# experimental.net
KiCad netlist of a schematic drawn in EAGLE
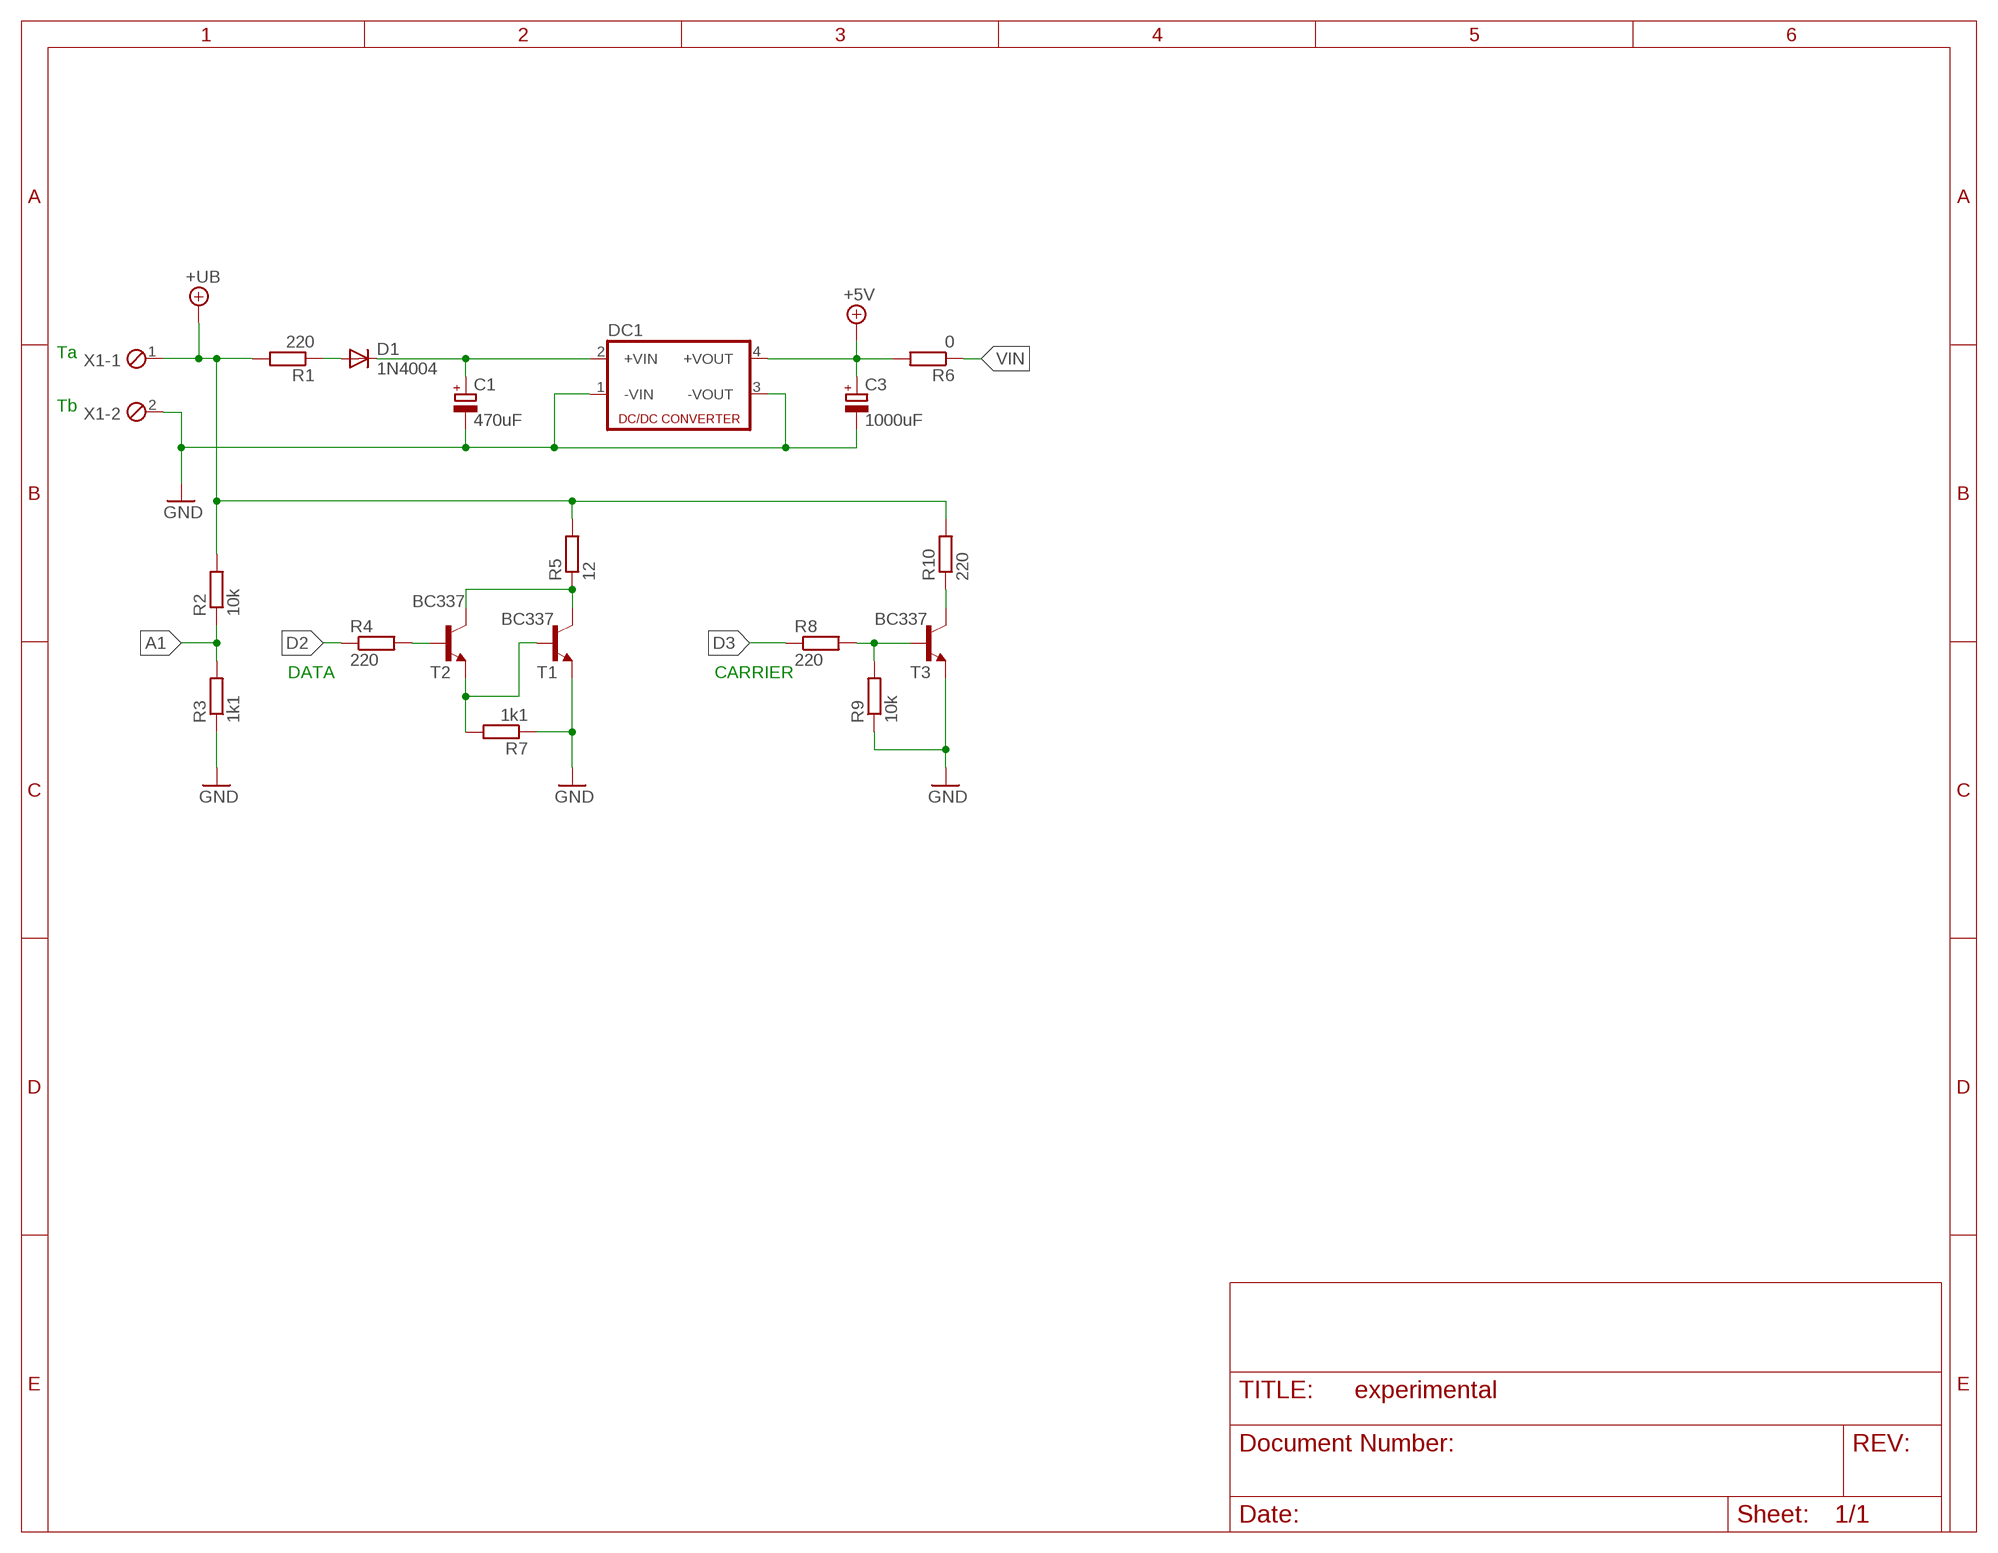
[diagram p0: schematic, sheet 1]

(export (version "E")
  (design (tool "Eeschema 10.0.6"))
  (components
    (comp (ref "C1")
      (value "470uF")
      (footprint "eagle-import:EB20D")
      (libsource (lib "eagle-import") (part "CPOL-EUE10-20"))
    )
    (comp (ref "C3")
      (value "1000uF")
      (footprint "eagle-import:EB20D")
      (libsource (lib "eagle-import") (part "CPOL-EUE10-20"))
    )
    (comp (ref "D1")
      (value "1N4004")
      (footprint "eagle-import:DO41-10")
      (libsource (lib "eagle-import") (part "1N4004"))
    )
    (comp (ref "DC1")
      (value "NME")
      (footprint "eagle-import:NME")
      (fields (field (name "MF") "C & D TECHNOLOGIES, INC") (field (name "MPN") "NME1205D"))
      (libsource (lib "eagle-import") (part "NME"))
    )
    (comp (ref "R1")
      (value "220")
      (footprint "eagle-import:0204_7")
      (libsource (lib "eagle-import") (part "R-EU_0204/7"))
    )
    (comp (ref "R2")
      (value "10k")
      (footprint "eagle-import:0204_7")
      (libsource (lib "eagle-import") (part "R-EU_0204/7"))
    )
    (comp (ref "R3")
      (value "1k1")
      (footprint "eagle-import:0204_7")
      (libsource (lib "eagle-import") (part "R-EU_0204/7"))
    )
    (comp (ref "R4")
      (value "220")
      (footprint "eagle-import:0204_7")
      (libsource (lib "eagle-import") (part "R-EU_0204/7"))
    )
    (comp (ref "R5")
      (value "12")
      (footprint "eagle-import:0204_7")
      (libsource (lib "eagle-import") (part "R-EU_0204/7"))
    )
    (comp (ref "R6")
      (value "0")
      (footprint "eagle-import:0204_7")
      (libsource (lib "eagle-import") (part "R-EU_0204/7"))
    )
    (comp (ref "R7")
      (value "1k1")
      (footprint "eagle-import:0204_7")
      (libsource (lib "eagle-import") (part "R-EU_0204/7"))
    )
    (comp (ref "R8")
      (value "220")
      (footprint "eagle-import:0204_7")
      (libsource (lib "eagle-import") (part "R-EU_0204/7"))
    )
    (comp (ref "R9")
      (value "10k")
      (footprint "eagle-import:0204_7")
      (libsource (lib "eagle-import") (part "R-EU_0204/7"))
    )
    (comp (ref "R10")
      (value "220")
      (footprint "eagle-import:0204_7")
      (libsource (lib "eagle-import") (part "R-EU_0204/7"))
    )
    (comp (ref "T1")
      (value "BC337")
      (footprint "eagle-import:TO92")
      (libsource (lib "eagle-import") (part "BC337"))
    )
    (comp (ref "T2")
      (value "BC337")
      (footprint "eagle-import:TO92")
      (libsource (lib "eagle-import") (part "BC337"))
    )
    (comp (ref "T3")
      (value "BC337")
      (footprint "eagle-import:TO92")
      (libsource (lib "eagle-import") (part "BC337"))
    )
    (comp (ref "X1")
      (value "MPT2")
      (footprint "eagle-import:2POL254")
      (libsource (lib "eagle-import") (part "MPT2"))
    )
  )
  (nets
    (net (code "1") (name "+5V") (class "Default")
      (node (ref "C3") (pin "+") (pinfunction "+_+") (pintype "passive"))
      (node (ref "DC1") (pin "4") (pinfunction "+VOUT_4") (pintype "passive"))
      (node (ref "R6") (pin "2") (pinfunction "2_2") (pintype "passive"))
    )
    (net (code "2") (name "+UB") (class "Default")
      (node (ref "R1") (pin "2") (pinfunction "2_2") (pintype "passive"))
      (node (ref "R10") (pin "2") (pinfunction "2_2") (pintype "passive"))
      (node (ref "R2") (pin "2") (pinfunction "2_2") (pintype "passive"))
      (node (ref "R5") (pin "2") (pinfunction "2_2") (pintype "passive"))
      (node (ref "X1") (pin "1") (pinfunction "1_1") (pintype "passive"))
    )
    (net (code "3") (name "A1") (class "Default")
      (node (ref "R2") (pin "1") (pinfunction "1_1") (pintype "passive"))
      (node (ref "R3") (pin "2") (pinfunction "2_2") (pintype "passive"))
    )
    (net (code "4") (name "D2") (class "Default")
      (node (ref "R4") (pin "1") (pinfunction "1_1") (pintype "passive"))
    )
    (net (code "5") (name "D3") (class "Default")
      (node (ref "R8") (pin "1") (pinfunction "1_1") (pintype "passive"))
    )
    (net (code "6") (name "GND") (class "Default")
      (node (ref "C1") (pin "-") (pinfunction "-_-") (pintype "passive"))
      (node (ref "C3") (pin "-") (pinfunction "-_-") (pintype "passive"))
      (node (ref "DC1") (pin "1") (pinfunction "-VIN_1") (pintype "passive"))
      (node (ref "DC1") (pin "3") (pinfunction "-VOUT_3") (pintype "passive"))
      (node (ref "R3") (pin "1") (pinfunction "1_1") (pintype "passive"))
      (node (ref "R7") (pin "1") (pinfunction "1_1") (pintype "passive"))
      (node (ref "R9") (pin "1") (pinfunction "1_1") (pintype "passive"))
      (node (ref "T1") (pin "1") (pinfunction "E_1") (pintype "passive"))
      (node (ref "T3") (pin "1") (pinfunction "E_1") (pintype "passive"))
      (node (ref "X1") (pin "2") (pinfunction "1_2") (pintype "passive"))
    )
    (net (code "7") (name "Net-(D1-PadA)") (class "Default")
      (node (ref "D1") (pin "A") (pinfunction "A_A") (pintype "passive"))
      (node (ref "R1") (pin "1") (pinfunction "1_1") (pintype "passive"))
    )
    (net (code "8") (name "Net-(DC1-+VIN)") (class "Default")
      (node (ref "C1") (pin "+") (pinfunction "+_+") (pintype "passive"))
      (node (ref "D1") (pin "C") (pinfunction "C_C") (pintype "passive"))
      (node (ref "DC1") (pin "2") (pinfunction "+VIN_2") (pintype "passive"))
    )
    (net (code "9") (name "Net-(T1-B)") (class "Default")
      (node (ref "R7") (pin "2") (pinfunction "2_2") (pintype "passive"))
      (node (ref "T1") (pin "2") (pinfunction "B_2") (pintype "passive"))
      (node (ref "T2") (pin "1") (pinfunction "E_1") (pintype "passive"))
    )
    (net (code "10") (name "Net-(T1-C)") (class "Default")
      (node (ref "R5") (pin "1") (pinfunction "1_1") (pintype "passive"))
      (node (ref "T1") (pin "3") (pinfunction "C_3") (pintype "passive"))
      (node (ref "T2") (pin "3") (pinfunction "C_3") (pintype "passive"))
    )
    (net (code "11") (name "Net-(T2-B)") (class "Default")
      (node (ref "R4") (pin "2") (pinfunction "2_2") (pintype "passive"))
      (node (ref "T2") (pin "2") (pinfunction "B_2") (pintype "passive"))
    )
    (net (code "12") (name "Net-(T3-B)") (class "Default")
      (node (ref "R8") (pin "2") (pinfunction "2_2") (pintype "passive"))
      (node (ref "R9") (pin "2") (pinfunction "2_2") (pintype "passive"))
      (node (ref "T3") (pin "2") (pinfunction "B_2") (pintype "passive"))
    )
    (net (code "13") (name "Net-(T3-C)") (class "Default")
      (node (ref "R10") (pin "1") (pinfunction "1_1") (pintype "passive"))
      (node (ref "T3") (pin "3") (pinfunction "C_3") (pintype "passive"))
    )
    (net (code "14") (name "VIN") (class "Default")
      (node (ref "R6") (pin "1") (pinfunction "1_1") (pintype "passive"))
    )
  )
)
